# frc_operator_interface.net
KiCad netlist of a schematic drawn in EAGLE
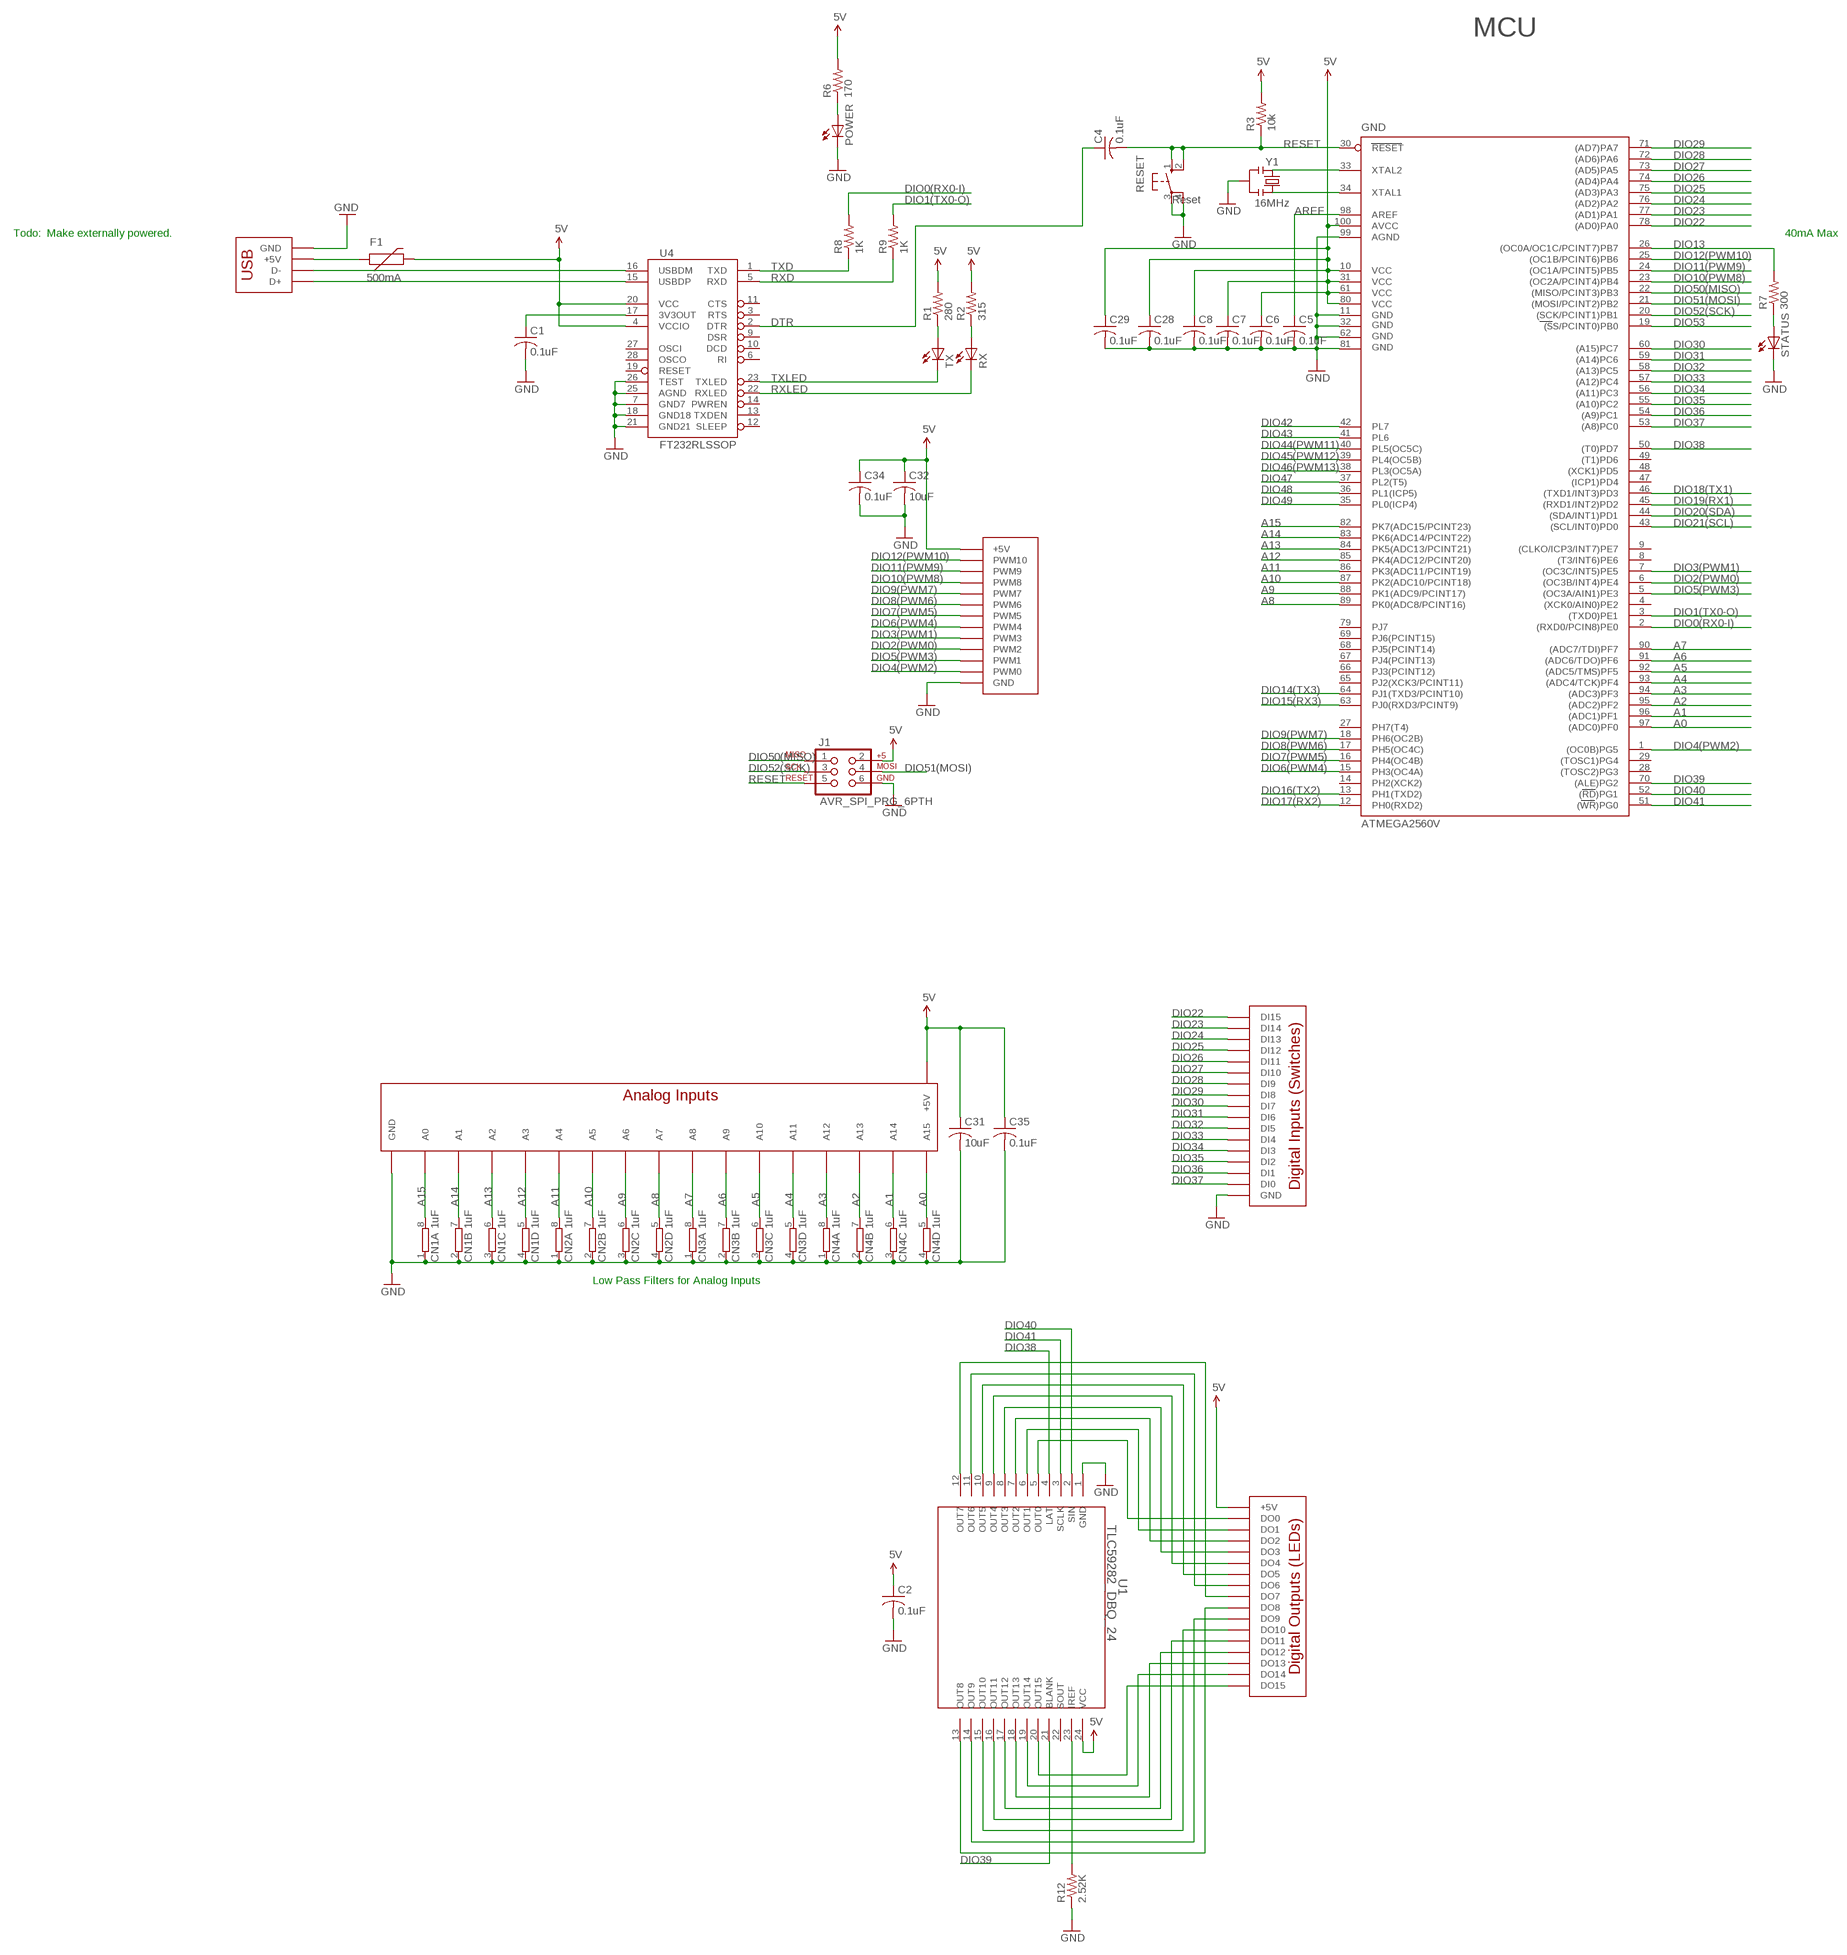
[diagram p0: schematic, sheet 1]

(export (version "E")
  (design (tool "Eeschema 10.0.6"))
  (components
    (comp (ref "C1")
      (value "0.1uF")
      (footprint "eagle-import:C1206")
      (libsource (lib "eagle-import") (part "C-USC1206"))
    )
    (comp (ref "C2")
      (value "0.1uF")
      (footprint "eagle-import:C1206")
      (libsource (lib "eagle-import") (part "C-USC1206"))
    )
    (comp (ref "C4")
      (value "0.1uF")
      (footprint "eagle-import:C1206")
      (libsource (lib "eagle-import") (part "C-USC1206"))
    )
    (comp (ref "C5")
      (value "0.1uF")
      (footprint "eagle-import:C1206")
      (libsource (lib "eagle-import") (part "C-USC1206"))
    )
    (comp (ref "C6")
      (value "0.1uF")
      (footprint "eagle-import:C1206")
      (libsource (lib "eagle-import") (part "C-USC1206"))
    )
    (comp (ref "C7")
      (value "0.1uF")
      (footprint "eagle-import:C1206")
      (libsource (lib "eagle-import") (part "C-USC1206"))
    )
    (comp (ref "C8")
      (value "0.1uF")
      (footprint "eagle-import:C1206")
      (libsource (lib "eagle-import") (part "C-USC1206"))
    )
    (comp (ref "C28")
      (value "0.1uF")
      (footprint "eagle-import:C1206")
      (libsource (lib "eagle-import") (part "C-USC1206"))
    )
    (comp (ref "C29")
      (value "0.1uF")
      (footprint "eagle-import:C1206")
      (libsource (lib "eagle-import") (part "C-USC1206"))
    )
    (comp (ref "C31")
      (value "10uF")
      (footprint "eagle-import:C1206")
      (libsource (lib "eagle-import") (part "C-USC1206"))
    )
    (comp (ref "C32")
      (value "10uF")
      (footprint "eagle-import:C1206")
      (libsource (lib "eagle-import") (part "C-USC1206"))
    )
    (comp (ref "C34")
      (value "0.1uF")
      (footprint "eagle-import:C1206")
      (libsource (lib "eagle-import") (part "C-USC1206"))
    )
    (comp (ref "C35")
      (value "0.1uF")
      (footprint "eagle-import:C1206")
      (libsource (lib "eagle-import") (part "C-USC1206"))
    )
    (comp (ref "CN1")
      (value "1uF")
      (footprint "eagle-import:EXB38V")
      (libsource (lib "eagle-import") (part "4R-NEXB38V"))
    )
    (comp (ref "CN2")
      (value "1uF")
      (footprint "eagle-import:EXB38V")
      (libsource (lib "eagle-import") (part "4R-NEXB38V"))
    )
    (comp (ref "CN3")
      (value "1uF")
      (footprint "eagle-import:EXB38V")
      (libsource (lib "eagle-import") (part "4R-NEXB38V"))
    )
    (comp (ref "CN4")
      (value "1uF")
      (footprint "eagle-import:EXB38V")
      (libsource (lib "eagle-import") (part "4R-NEXB38V"))
    )
    (comp (ref "F1")
      (value "500mA")
      (footprint "eagle-import:PTC-1206")
      (libsource (lib "eagle-import") (part "PTCSMD"))
    )
    (comp (ref "GND")
      (value "ATMEGA2560AU")
      (footprint "eagle-import:TQFP100")
      (libsource (lib "eagle-import") (part "ATMEGA2560AU"))
    )
    (comp (ref "J1")
      (value "AVR_SPI_PRG_6PTH")
      (footprint "eagle-import:2X3")
      (libsource (lib "eagle-import") (part "AVR_SPI_PRG_6PTH"))
    )
    (comp (ref "POWER")
      (value "LED3MM")
      (footprint "eagle-import:LED3MM")
      (libsource (lib "eagle-import") (part "LED3MM"))
    )
    (comp (ref "R1")
      (value "280")
      (footprint "eagle-import:M1206")
      (libsource (lib "eagle-import") (part "R-US_M1206"))
    )
    (comp (ref "R2")
      (value "315")
      (footprint "eagle-import:M1206")
      (libsource (lib "eagle-import") (part "R-US_M1206"))
    )
    (comp (ref "R3")
      (value "10k")
      (footprint "eagle-import:M1206")
      (libsource (lib "eagle-import") (part "R-US_M1206"))
    )
    (comp (ref "R6")
      (value "170")
      (footprint "eagle-import:M1206")
      (libsource (lib "eagle-import") (part "R-US_M1206"))
    )
    (comp (ref "R7")
      (value "300")
      (footprint "eagle-import:M1206")
      (libsource (lib "eagle-import") (part "R-US_M1206"))
    )
    (comp (ref "R8")
      (value "1K")
      (footprint "eagle-import:M1206")
      (libsource (lib "eagle-import") (part "R-US_M1206"))
    )
    (comp (ref "R9")
      (value "1K")
      (footprint "eagle-import:M1206")
      (libsource (lib "eagle-import") (part "R-US_M1206"))
    )
    (comp (ref "R12")
      (value "2.52K")
      (footprint "eagle-import:M1206")
      (libsource (lib "eagle-import") (part "R-US_M1206"))
    )
    (comp (ref "RESET")
      (value "10-XX")
      (footprint "eagle-import:B3F-10XX")
      (fields (field (name "MPN") "B3F-1000"))
      (libsource (lib "eagle-import") (part "10-XX"))
    )
    (comp (ref "RX")
      (value "LED3MM")
      (footprint "eagle-import:LED3MM")
      (libsource (lib "eagle-import") (part "LED3MM"))
    )
    (comp (ref "STATUS")
      (value "LED3MM")
      (footprint "eagle-import:LED3MM")
      (libsource (lib "eagle-import") (part "LED3MM"))
    )
    (comp (ref "TX")
      (value "LED3MM")
      (footprint "eagle-import:LED3MM")
      (libsource (lib "eagle-import") (part "LED3MM"))
    )
    (comp (ref "U$2")
      (value "DIGITALIN")
      (footprint "eagle-import:DIGITALIN")
      (libsource (lib "eagle-import") (part "DIGITALIN"))
    )
    (comp (ref "U$10")
      (value "PWMHEADER")
      (footprint "eagle-import:PWMHEADER")
      (libsource (lib "eagle-import") (part "PWMHEADER"))
    )
    (comp (ref "U$11")
      (value "DIGITALOUTPUTS")
      (footprint "eagle-import:DIGITALOUT")
      (libsource (lib "eagle-import") (part "DIGITALOUTPUTS"))
    )
    (comp (ref "U$12")
      (value "ANALOGHEADER")
      (footprint "eagle-import:ANALOGHEADER")
      (libsource (lib "eagle-import") (part "ANALOGHEADER"))
    )
    (comp (ref "U$14")
      (value "UE27BC54130-USB")
      (footprint "eagle-import:UE27BC54130-USB")
      (libsource (lib "eagle-import") (part "UE27BC54130-USB"))
    )
    (comp (ref "U1")
      (value "TLC59282_DBQ_24")
      (footprint "eagle-import:DBQ24")
      (fields
        (field (name "GENERIC_PART_NUMBER") "TLC59282")
        (field (name "MANUFACTURER") "Texas Instruments")
        (field (name "MANUFACTURER_PART_NUMBER") "tlc59282_dbq_24")
      )
      (libsource (lib "eagle-import") (part "TLC59282_DBQ_24"))
    )
    (comp (ref "U4")
      (value "FT232RLSSOP")
      (footprint "eagle-import:SSOP28DB")
      (libsource (lib "eagle-import") (part "FT232RLSSOP"))
    )
    (comp (ref "Y1")
      (value "RESONATORSMD")
      (footprint "eagle-import:RESONATOR-SMD")
      (libsource (lib "eagle-import") (part "RESONATORSMD"))
    )
  )
  (nets
    (net (code "1") (name "/A0") (class "Default")
      (node (ref "CN4") (pin "5") (pinfunction "2_5") (pintype "passive"))
      (node (ref "GND") (pin "97") (pinfunction "(ADC0)PF0_97") (pintype "bidirectional"))
      (node (ref "U$12") (pin "15") (pinfunction "A15_15") (pintype "bidirectional"))
    )
    (net (code "2") (name "/A1") (class "Default")
      (node (ref "CN4") (pin "6") (pinfunction "2_6") (pintype "passive"))
      (node (ref "GND") (pin "96") (pinfunction "(ADC1)PF1_96") (pintype "bidirectional"))
      (node (ref "U$12") (pin "14") (pinfunction "A14_14") (pintype "bidirectional"))
    )
    (net (code "3") (name "/A2") (class "Default")
      (node (ref "CN4") (pin "7") (pinfunction "2_7") (pintype "passive"))
      (node (ref "GND") (pin "95") (pinfunction "(ADC2)PF2_95") (pintype "bidirectional"))
      (node (ref "U$12") (pin "13") (pinfunction "A13_13") (pintype "bidirectional"))
    )
    (net (code "4") (name "/A3") (class "Default")
      (node (ref "CN4") (pin "8") (pinfunction "2_8") (pintype "passive"))
      (node (ref "GND") (pin "94") (pinfunction "(ADC3)PF3_94") (pintype "bidirectional"))
      (node (ref "U$12") (pin "12") (pinfunction "A12_12") (pintype "bidirectional"))
    )
    (net (code "5") (name "/A4") (class "Default")
      (node (ref "CN3") (pin "5") (pinfunction "2_5") (pintype "passive"))
      (node (ref "GND") (pin "93") (pinfunction "(ADC4/TCK)PF4_93") (pintype "bidirectional"))
      (node (ref "U$12") (pin "11") (pinfunction "A11_11") (pintype "bidirectional"))
    )
    (net (code "6") (name "/A5") (class "Default")
      (node (ref "CN3") (pin "6") (pinfunction "2_6") (pintype "passive"))
      (node (ref "GND") (pin "92") (pinfunction "(ADC5/TMS)PF5_92") (pintype "bidirectional"))
      (node (ref "U$12") (pin "10") (pinfunction "A10_10") (pintype "bidirectional"))
    )
    (net (code "7") (name "/A6") (class "Default")
      (node (ref "CN3") (pin "7") (pinfunction "2_7") (pintype "passive"))
      (node (ref "GND") (pin "91") (pinfunction "(ADC6/TDO)PF6_91") (pintype "bidirectional"))
      (node (ref "U$12") (pin "9") (pinfunction "A9_9") (pintype "bidirectional"))
    )
    (net (code "8") (name "/A7") (class "Default")
      (node (ref "CN3") (pin "8") (pinfunction "2_8") (pintype "passive"))
      (node (ref "GND") (pin "90") (pinfunction "(ADC7/TDI)PF7_90") (pintype "bidirectional"))
      (node (ref "U$12") (pin "8") (pinfunction "A8_8") (pintype "bidirectional"))
    )
    (net (code "9") (name "/A8") (class "Default")
      (node (ref "CN2") (pin "5") (pinfunction "2_5") (pintype "passive"))
      (node (ref "GND") (pin "89") (pinfunction "PK0(ADC8/PCINT16)_89") (pintype "bidirectional"))
      (node (ref "U$12") (pin "7") (pinfunction "A7_7") (pintype "bidirectional"))
    )
    (net (code "10") (name "/A9") (class "Default")
      (node (ref "CN2") (pin "6") (pinfunction "2_6") (pintype "passive"))
      (node (ref "GND") (pin "88") (pinfunction "PK1(ADC9/PCINT17)_88") (pintype "bidirectional"))
      (node (ref "U$12") (pin "6") (pinfunction "A6_6") (pintype "bidirectional"))
    )
    (net (code "11") (name "/A10") (class "Default")
      (node (ref "CN2") (pin "7") (pinfunction "2_7") (pintype "passive"))
      (node (ref "GND") (pin "87") (pinfunction "PK2(ADC10/PCINT18)_87") (pintype "bidirectional"))
      (node (ref "U$12") (pin "5") (pinfunction "A5_5") (pintype "bidirectional"))
    )
    (net (code "12") (name "/A11") (class "Default")
      (node (ref "CN2") (pin "8") (pinfunction "2_8") (pintype "passive"))
      (node (ref "GND") (pin "86") (pinfunction "PK3(ADC11/PCINT19)_86") (pintype "bidirectional"))
      (node (ref "U$12") (pin "4") (pinfunction "A4_4") (pintype "bidirectional"))
    )
    (net (code "13") (name "/A12") (class "Default")
      (node (ref "CN1") (pin "5") (pinfunction "2_5") (pintype "passive"))
      (node (ref "GND") (pin "85") (pinfunction "PK4(ADC12/PCINT20)_85") (pintype "bidirectional"))
      (node (ref "U$12") (pin "3") (pinfunction "A3_3") (pintype "bidirectional"))
    )
    (net (code "14") (name "/A13") (class "Default")
      (node (ref "CN1") (pin "6") (pinfunction "2_6") (pintype "passive"))
      (node (ref "GND") (pin "84") (pinfunction "PK5(ADC13/PCINT21)_84") (pintype "bidirectional"))
      (node (ref "U$12") (pin "2") (pinfunction "A2_2") (pintype "bidirectional"))
    )
    (net (code "15") (name "/A14") (class "Default")
      (node (ref "CN1") (pin "7") (pinfunction "2_7") (pintype "passive"))
      (node (ref "GND") (pin "83") (pinfunction "PK6(ADC14/PCINT22)_83") (pintype "bidirectional"))
      (node (ref "U$12") (pin "1") (pinfunction "A1_1") (pintype "bidirectional"))
    )
    (net (code "16") (name "/A15") (class "Default")
      (node (ref "CN1") (pin "8") (pinfunction "2_8") (pintype "passive"))
      (node (ref "GND") (pin "82") (pinfunction "PK7(ADC15/PCINT23)_82") (pintype "bidirectional"))
      (node (ref "U$12") (pin "0") (pinfunction "A0_0") (pintype "bidirectional"))
    )
    (net (code "17") (name "/AREF") (class "Default")
      (node (ref "C5") (pin "1") (pinfunction "1_1") (pintype "passive"))
      (node (ref "GND") (pin "98") (pinfunction "AREF_98") (pintype "bidirectional"))
    )
    (net (code "18") (name "/DIO0(RX0-I)") (class "Default")
      (node (ref "GND") (pin "2") (pinfunction "(RXD0/PCIN8)PE0_2") (pintype "bidirectional"))
      (node (ref "R8") (pin "2") (pinfunction "2_2") (pintype "passive"))
    )
    (net (code "19") (name "/DIO1(TX0-O)") (class "Default")
      (node (ref "GND") (pin "3") (pinfunction "(TXD0)PE1_3") (pintype "bidirectional"))
      (node (ref "R9") (pin "2") (pinfunction "2_2") (pintype "passive"))
    )
    (net (code "20") (name "/DIO2(PWM0)") (class "Default")
      (node (ref "GND") (pin "6") (pinfunction "(OC3B/INT4)PE4_6") (pintype "bidirectional"))
      (node (ref "U$10") (pin "2") (pinfunction "PWM2_2") (pintype "output"))
    )
    (net (code "21") (name "/DIO3(PWM1)") (class "Default")
      (node (ref "GND") (pin "7") (pinfunction "(OC3C/INT5)PE5_7") (pintype "bidirectional"))
      (node (ref "U$10") (pin "3") (pinfunction "PWM3_3") (pintype "output"))
    )
    (net (code "22") (name "/DIO4(PWM2)") (class "Default")
      (node (ref "GND") (pin "1") (pinfunction "(OC0B)PG5_1") (pintype "bidirectional"))
      (node (ref "U$10") (pin "0") (pinfunction "PWM0_0") (pintype "output"))
    )
    (net (code "23") (name "/DIO5(PWM3)") (class "Default")
      (node (ref "GND") (pin "5") (pinfunction "(OC3A/AIN1)PE3_5") (pintype "bidirectional"))
      (node (ref "U$10") (pin "1") (pinfunction "PWM1_1") (pintype "output"))
    )
    (net (code "24") (name "/DIO6(PWM4)") (class "Default")
      (node (ref "GND") (pin "15") (pinfunction "PH3(OC4A)_15") (pintype "bidirectional"))
      (node (ref "U$10") (pin "4") (pinfunction "PWM4_4") (pintype "output"))
    )
    (net (code "25") (name "/DIO7(PWM5)") (class "Default")
      (node (ref "GND") (pin "16") (pinfunction "PH4(OC4B)_16") (pintype "bidirectional"))
      (node (ref "U$10") (pin "5") (pinfunction "PWM5_5") (pintype "output"))
    )
    (net (code "26") (name "/DIO8(PWM6)") (class "Default")
      (node (ref "GND") (pin "17") (pinfunction "PH5(OC4C)_17") (pintype "bidirectional"))
      (node (ref "U$10") (pin "6") (pinfunction "PWM6_6") (pintype "output"))
    )
    (net (code "27") (name "/DIO9(PWM7)") (class "Default")
      (node (ref "GND") (pin "18") (pinfunction "PH6(OC2B)_18") (pintype "bidirectional"))
      (node (ref "U$10") (pin "7") (pinfunction "PWM7_7") (pintype "output"))
    )
    (net (code "28") (name "/DIO10(PWM8)") (class "Default")
      (node (ref "GND") (pin "23") (pinfunction "(OC2A/PCINT4)PB4_23") (pintype "bidirectional"))
      (node (ref "U$10") (pin "8") (pinfunction "PWM8_8") (pintype "output"))
    )
    (net (code "29") (name "/DIO11(PWM9)") (class "Default")
      (node (ref "GND") (pin "24") (pinfunction "(OC1A/PCINT5)PB5_24") (pintype "bidirectional"))
      (node (ref "U$10") (pin "9") (pinfunction "PWM9_9") (pintype "output"))
    )
    (net (code "30") (name "/DIO12(PWM10)") (class "Default")
      (node (ref "GND") (pin "25") (pinfunction "(OC1B/PCINT6)PB6_25") (pintype "bidirectional"))
      (node (ref "U$10") (pin "10") (pinfunction "PWM10_10") (pintype "output"))
    )
    (net (code "31") (name "/DIO13") (class "Default")
      (node (ref "GND") (pin "26") (pinfunction "(OC0A/OC1C/PCINT7)PB7_26") (pintype "bidirectional"))
      (node (ref "R7") (pin "2") (pinfunction "2_2") (pintype "passive"))
    )
    (net (code "32") (name "/DIO14(TX3)") (class "Default")
      (node (ref "GND") (pin "64") (pinfunction "PJ1(TXD3/PCINT10)_64") (pintype "bidirectional"))
    )
    (net (code "33") (name "/DIO15(RX3)") (class "Default")
      (node (ref "GND") (pin "63") (pinfunction "PJ0(RXD3/PCINT9)_63") (pintype "bidirectional"))
    )
    (net (code "34") (name "/DIO16(TX2)") (class "Default")
      (node (ref "GND") (pin "13") (pinfunction "PH1(TXD2)_13") (pintype "bidirectional"))
    )
    (net (code "35") (name "/DIO17(RX2)") (class "Default")
      (node (ref "GND") (pin "12") (pinfunction "PH0(RXD2)_12") (pintype "bidirectional"))
    )
    (net (code "36") (name "/DIO18(TX1)") (class "Default")
      (node (ref "GND") (pin "46") (pinfunction "(TXD1/INT3)PD3_46") (pintype "bidirectional"))
    )
    (net (code "37") (name "/DIO19(RX1)") (class "Default")
      (node (ref "GND") (pin "45") (pinfunction "(RXD1/INT2)PD2_45") (pintype "bidirectional"))
    )
    (net (code "38") (name "/DIO20(SDA)") (class "Default")
      (node (ref "GND") (pin "44") (pinfunction "(SDA/INT1)PD1_44") (pintype "bidirectional"))
    )
    (net (code "39") (name "/DIO21(SCL)") (class "Default")
      (node (ref "GND") (pin "43") (pinfunction "(SCL/INT0)PD0_43") (pintype "bidirectional"))
    )
    (net (code "40") (name "/DIO22") (class "Default")
      (node (ref "GND") (pin "78") (pinfunction "(AD0)PA0_78") (pintype "bidirectional"))
      (node (ref "U$2") (pin "DI15") (pinfunction "DI15_DI15") (pintype "bidirectional"))
    )
    (net (code "41") (name "/DIO23") (class "Default")
      (node (ref "GND") (pin "77") (pinfunction "(AD1)PA1_77") (pintype "bidirectional"))
      (node (ref "U$2") (pin "DI14") (pinfunction "DI14_DI14") (pintype "bidirectional"))
    )
    (net (code "42") (name "/DIO24") (class "Default")
      (node (ref "GND") (pin "76") (pinfunction "(AD2)PA2_76") (pintype "bidirectional"))
      (node (ref "U$2") (pin "DI13") (pinfunction "DI13_DI13") (pintype "bidirectional"))
    )
    (net (code "43") (name "/DIO25") (class "Default")
      (node (ref "GND") (pin "75") (pinfunction "(AD3)PA3_75") (pintype "bidirectional"))
      (node (ref "U$2") (pin "DI12") (pinfunction "DI12_DI12") (pintype "bidirectional"))
    )
    (net (code "44") (name "/DIO26") (class "Default")
      (node (ref "GND") (pin "74") (pinfunction "(AD4)PA4_74") (pintype "bidirectional"))
      (node (ref "U$2") (pin "DI11") (pinfunction "DI11_DI11") (pintype "bidirectional"))
    )
    (net (code "45") (name "/DIO27") (class "Default")
      (node (ref "GND") (pin "73") (pinfunction "(AD5)PA5_73") (pintype "bidirectional"))
      (node (ref "U$2") (pin "DI10") (pinfunction "DI10_DI10") (pintype "bidirectional"))
    )
    (net (code "46") (name "/DIO28") (class "Default")
      (node (ref "GND") (pin "72") (pinfunction "(AD6)PA6_72") (pintype "bidirectional"))
      (node (ref "U$2") (pin "DI9") (pinfunction "DI9_DI9") (pintype "bidirectional"))
    )
    (net (code "47") (name "/DIO29") (class "Default")
      (node (ref "GND") (pin "71") (pinfunction "(AD7)PA7_71") (pintype "bidirectional"))
      (node (ref "U$2") (pin "DI8") (pinfunction "DI8_DI8") (pintype "bidirectional"))
    )
    (net (code "48") (name "/DIO30") (class "Default")
      (node (ref "GND") (pin "60") (pinfunction "(A15)PC7_60") (pintype "bidirectional"))
      (node (ref "U$2") (pin "DI7") (pinfunction "DI7_DI7") (pintype "bidirectional"))
    )
    (net (code "49") (name "/DIO31") (class "Default")
      (node (ref "GND") (pin "59") (pinfunction "(A14)PC6_59") (pintype "bidirectional"))
      (node (ref "U$2") (pin "DI6") (pinfunction "DI6_DI6") (pintype "bidirectional"))
    )
    (net (code "50") (name "/DIO32") (class "Default")
      (node (ref "GND") (pin "58") (pinfunction "(A13)PC5_58") (pintype "bidirectional"))
      (node (ref "U$2") (pin "DI5") (pinfunction "DI5_DI5") (pintype "bidirectional"))
    )
    (net (code "51") (name "/DIO33") (class "Default")
      (node (ref "GND") (pin "57") (pinfunction "(A12)PC4_57") (pintype "bidirectional"))
      (node (ref "U$2") (pin "DI4") (pinfunction "DI4_DI4") (pintype "bidirectional"))
    )
    (net (code "52") (name "/DIO34") (class "Default")
      (node (ref "GND") (pin "56") (pinfunction "(A11)PC3_56") (pintype "bidirectional"))
      (node (ref "U$2") (pin "DI3") (pinfunction "DI3_DI3") (pintype "bidirectional"))
    )
    (net (code "53") (name "/DIO35") (class "Default")
      (node (ref "GND") (pin "55") (pinfunction "(A10)PC2_55") (pintype "bidirectional"))
      (node (ref "U$2") (pin "DI2") (pinfunction "DI2_DI2") (pintype "bidirectional"))
    )
    (net (code "54") (name "/DIO36") (class "Default")
      (node (ref "GND") (pin "54") (pinfunction "(A9)PC1_54") (pintype "bidirectional"))
      (node (ref "U$2") (pin "DI1") (pinfunction "DI1_DI1") (pintype "bidirectional"))
    )
    (net (code "55") (name "/DIO37") (class "Default")
      (node (ref "GND") (pin "53") (pinfunction "(A8)PC0_53") (pintype "bidirectional"))
      (node (ref "U$2") (pin "DI0") (pinfunction "DI0_DI0") (pintype "bidirectional"))
    )
    (net (code "56") (name "/DIO38") (class "Default")
      (node (ref "GND") (pin "50") (pinfunction "(T0)PD7_50") (pintype "bidirectional"))
      (node (ref "U1") (pin "4") (pinfunction "LAT_4") (pintype "input"))
    )
    (net (code "57") (name "/DIO39") (class "Default")
      (node (ref "GND") (pin "70") (pinfunction "(ALE)PG2_70") (pintype "bidirectional"))
      (node (ref "U1") (pin "21") (pinfunction "BLANK_21") (pintype "input"))
    )
    (net (code "58") (name "/DIO40") (class "Default")
      (node (ref "GND") (pin "52") (pinfunction "(RD)PG1_52") (pintype "bidirectional"))
      (node (ref "U1") (pin "2") (pinfunction "SIN_2") (pintype "input"))
    )
    (net (code "59") (name "/DIO41") (class "Default")
      (node (ref "GND") (pin "51") (pinfunction "(WR)PG0_51") (pintype "bidirectional"))
      (node (ref "U1") (pin "3") (pinfunction "SCLK_3") (pintype "input"))
    )
    (net (code "60") (name "/DIO42") (class "Default")
      (node (ref "GND") (pin "42") (pinfunction "PL7_42") (pintype "bidirectional"))
    )
    (net (code "61") (name "/DIO43") (class "Default")
      (node (ref "GND") (pin "41") (pinfunction "PL6_41") (pintype "bidirectional"))
    )
    (net (code "62") (name "/DIO44(PWM11)") (class "Default")
      (node (ref "GND") (pin "40") (pinfunction "PL5(OC5C)_40") (pintype "bidirectional"))
    )
    (net (code "63") (name "/DIO45(PWM12)") (class "Default")
      (node (ref "GND") (pin "39") (pinfunction "PL4(OC5B)_39") (pintype "bidirectional"))
    )
    (net (code "64") (name "/DIO46(PWM13)") (class "Default")
      (node (ref "GND") (pin "38") (pinfunction "PL3(OC5A)_38") (pintype "bidirectional"))
    )
    (net (code "65") (name "/DIO47") (class "Default")
      (node (ref "GND") (pin "37") (pinfunction "PL2(T5)_37") (pintype "bidirectional"))
    )
    (net (code "66") (name "/DIO48") (class "Default")
      (node (ref "GND") (pin "36") (pinfunction "PL1(ICP5)_36") (pintype "bidirectional"))
    )
    (net (code "67") (name "/DIO49") (class "Default")
      (node (ref "GND") (pin "35") (pinfunction "PL0(ICP4)_35") (pintype "bidirectional"))
    )
    (net (code "68") (name "/DIO50(MISO)") (class "Default")
      (node (ref "GND") (pin "22") (pinfunction "(MISO/PCINT3)PB3_22") (pintype "bidirectional"))
      (node (ref "J1") (pin "1") (pinfunction "1_1") (pintype "passive"))
    )
    (net (code "69") (name "/DIO51(MOSI)") (class "Default")
      (node (ref "GND") (pin "21") (pinfunction "(MOSI/PCINT2)PB2_21") (pintype "bidirectional"))
      (node (ref "J1") (pin "4") (pinfunction "4_4") (pintype "passive"))
    )
    (net (code "70") (name "/DIO52(SCK)") (class "Default")
      (node (ref "GND") (pin "20") (pinfunction "(SCK/PCINT1)PB1_20") (pintype "bidirectional"))
      (node (ref "J1") (pin "3") (pinfunction "3_3") (pintype "passive"))
    )
    (net (code "71") (name "/DIO53") (class "Default")
      (node (ref "GND") (pin "19") (pinfunction "(SS/PCINT0)PB0_19") (pintype "bidirectional"))
    )
    (net (code "72") (name "/DTR") (class "Default")
      (node (ref "C4") (pin "1") (pinfunction "1_1") (pintype "passive"))
      (node (ref "U4") (pin "2") (pinfunction "DTR_2") (pintype "output"))
    )
    (net (code "73") (name "/RESET") (class "Default")
      (node (ref "C4") (pin "2") (pinfunction "2_2") (pintype "passive"))
      (node (ref "GND") (pin "30") (pinfunction "RESET_30") (pintype "input"))
      (node (ref "J1") (pin "5") (pinfunction "5_5") (pintype "passive"))
      (node (ref "R3") (pin "1") (pinfunction "1_1") (pintype "passive"))
      (node (ref "RESET") (pin "1") (pinfunction "S_1") (pintype "passive"))
      (node (ref "RESET") (pin "2") (pinfunction "S1_2") (pintype "passive"))
    )
    (net (code "74") (name "/RXD") (class "Default")
      (node (ref "R9") (pin "1") (pinfunction "1_1") (pintype "passive"))
      (node (ref "U4") (pin "5") (pinfunction "RXD_5") (pintype "input"))
    )
    (net (code "75") (name "/RXLED") (class "Default")
      (node (ref "RX") (pin "K") (pinfunction "C_K") (pintype "passive"))
      (node (ref "U4") (pin "22") (pinfunction "RXLED_22") (pintype "input"))
    )
    (net (code "76") (name "/TXD") (class "Default")
      (node (ref "R8") (pin "1") (pinfunction "1_1") (pintype "passive"))
      (node (ref "U4") (pin "1") (pinfunction "TXD_1") (pintype "output"))
    )
    (net (code "77") (name "/TXLED") (class "Default")
      (node (ref "TX") (pin "K") (pinfunction "C_K") (pintype "passive"))
      (node (ref "U4") (pin "23") (pinfunction "TXLED_23") (pintype "input"))
    )
    (net (code "78") (name "5V") (class "Default")
      (node (ref "C2") (pin "1") (pinfunction "1_1") (pintype "passive"))
      (node (ref "C28") (pin "1") (pinfunction "1_1") (pintype "passive"))
      (node (ref "C29") (pin "1") (pinfunction "1_1") (pintype "passive"))
      (node (ref "C31") (pin "1") (pinfunction "1_1") (pintype "passive"))
      (node (ref "C32") (pin "1") (pinfunction "1_1") (pintype "passive"))
      (node (ref "C34") (pin "1") (pinfunction "1_1") (pintype "passive"))
      (node (ref "C35") (pin "1") (pinfunction "1_1") (pintype "passive"))
      (node (ref "C6") (pin "1") (pinfunction "1_1") (pintype "passive"))
      (node (ref "C7") (pin "1") (pinfunction "1_1") (pintype "passive"))
      (node (ref "C8") (pin "1") (pinfunction "1_1") (pintype "passive"))
      (node (ref "F1") (pin "2") (pinfunction "2_2") (pintype "bidirectional"))
      (node (ref "GND") (pin "10") (pinfunction "VCC_10") (pintype "power_in"))
      (node (ref "GND") (pin "100") (pinfunction "AVCC_100") (pintype "power_in"))
      (node (ref "GND") (pin "31") (pinfunction "VCC1_31") (pintype "power_in"))
      (node (ref "GND") (pin "61") (pinfunction "VCC2_61") (pintype "power_in"))
      (node (ref "GND") (pin "80") (pinfunction "VCC3_80") (pintype "power_in"))
      (node (ref "J1") (pin "2") (pinfunction "2_2") (pintype "passive"))
      (node (ref "R1") (pin "2") (pinfunction "2_2") (pintype "passive"))
      (node (ref "R2") (pin "2") (pinfunction "2_2") (pintype "passive"))
      (node (ref "R3") (pin "2") (pinfunction "2_2") (pintype "passive"))
      (node (ref "R6") (pin "2") (pinfunction "2_2") (pintype "passive"))
      (node (ref "U$10") (pin "+5V@10") (pinfunction "+5V_+5V@10") (pintype "power_in"))
      (node (ref "U$10") (pin "+5V@11") (pinfunction "+5V_+5V@11") (pintype "power_in"))
      (node (ref "U$10") (pin "+5V@12") (pinfunction "+5V_+5V@12") (pintype "power_in"))
      (node (ref "U$10") (pin "+5V@13") (pinfunction "+5V_+5V@13") (pintype "power_in"))
      (node (ref "U$10") (pin "+5V@3") (pinfunction "+5V_+5V@3") (pintype "power_in"))
      (node (ref "U$10") (pin "+5V@4") (pinfunction "+5V_+5V@4") (pintype "power_in"))
      (node (ref "U$10") (pin "+5V@5") (pinfunction "+5V_+5V@5") (pintype "power_in"))
      (node (ref "U$10") (pin "+5V@6") (pinfunction "+5V_+5V@6") (pintype "power_in"))
      (node (ref "U$10") (pin "+5V@7") (pinfunction "+5V_+5V@7") (pintype "power_in"))
      (node (ref "U$10") (pin "+5V@8") (pinfunction "+5V_+5V@8") (pintype "power_in"))
      (node (ref "U$10") (pin "+5V@9") (pinfunction "+5V_+5V@9") (pintype "power_in"))
      (node (ref "U$11") (pin "+5V@0") (pinfunction "+5V_+5V@0") (pintype "power_in"))
      (node (ref "U$11") (pin "+5V@1") (pinfunction "+5V_+5V@1") (pintype "power_in"))
      (node (ref "U$11") (pin "+5V@10") (pinfunction "+5V_+5V@10") (pintype "power_in"))
      (node (ref "U$11") (pin "+5V@11") (pinfunction "+5V_+5V@11") (pintype "power_in"))
      (node (ref "U$11") (pin "+5V@12") (pinfunction "+5V_+5V@12") (pintype "power_in"))
      (node (ref "U$11") (pin "+5V@13") (pinfunction "+5V_+5V@13") (pintype "power_in"))
      (node (ref "U$11") (pin "+5V@14") (pinfunction "+5V_+5V@14") (pintype "power_in"))
      (node (ref "U$11") (pin "+5V@15") (pinfunction "+5V_+5V@15") (pintype "power_in"))
      (node (ref "U$11") (pin "+5V@2") (pinfunction "+5V_+5V@2") (pintype "power_in"))
      (node (ref "U$11") (pin "+5V@3") (pinfunction "+5V_+5V@3") (pintype "power_in"))
      (node (ref "U$11") (pin "+5V@4") (pinfunction "+5V_+5V@4") (pintype "power_in"))
      (node (ref "U$11") (pin "+5V@5") (pinfunction "+5V_+5V@5") (pintype "power_in"))
      (node (ref "U$11") (pin "+5V@6") (pinfunction "+5V_+5V@6") (pintype "power_in"))
      (node (ref "U$11") (pin "+5V@7") (pinfunction "+5V_+5V@7") (pintype "power_in"))
      (node (ref "U$11") (pin "+5V@8") (pinfunction "+5V_+5V@8") (pintype "power_in"))
      (node (ref "U$11") (pin "+5V@9") (pinfunction "+5V_+5V@9") (pintype "power_in"))
      (node (ref "U$12") (pin "+5V@0") (pinfunction "+5V_+5V@0") (pintype "bidirectional"))
      (node (ref "U$12") (pin "+5V@1") (pinfunction "+5V_+5V@1") (pintype "bidirectional"))
      (node (ref "U$12") (pin "+5V@10") (pinfunction "+5V_+5V@10") (pintype "bidirectional"))
      (node (ref "U$12") (pin "+5V@11") (pinfunction "+5V_+5V@11") (pintype "bidirectional"))
      (node (ref "U$12") (pin "+5V@12") (pinfunction "+5V_+5V@12") (pintype "bidirectional"))
      (node (ref "U$12") (pin "+5V@13") (pinfunction "+5V_+5V@13") (pintype "bidirectional"))
      (node (ref "U$12") (pin "+5V@14") (pinfunction "+5V_+5V@14") (pintype "bidirectional"))
      (node (ref "U$12") (pin "+5V@15") (pinfunction "+5V_+5V@15") (pintype "bidirectional"))
      (node (ref "U$12") (pin "+5V@2") (pinfunction "+5V_+5V@2") (pintype "bidirectional"))
      (node (ref "U$12") (pin "+5V@3") (pinfunction "+5V_+5V@3") (pintype "bidirectional"))
      (node (ref "U$12") (pin "+5V@4") (pinfunction "+5V_+5V@4") (pintype "bidirectional"))
      (node (ref "U$12") (pin "+5V@5") (pinfunction "+5V_+5V@5") (pintype "bidirectional"))
      (node (ref "U$12") (pin "+5V@6") (pinfunction "+5V_+5V@6") (pintype "bidirectional"))
      (node (ref "U$12") (pin "+5V@7") (pinfunction "+5V_+5V@7") (pintype "bidirectional"))
      (node (ref "U$12") (pin "+5V@8") (pinfunction "+5V_+5V@8") (pintype "bidirectional"))
      (node (ref "U$12") (pin "+5V@9") (pinfunction "+5V_+5V@9") (pintype "bidirectional"))
      (node (ref "U1") (pin "24") (pinfunction "VCC_24") (pintype "power_in"))
      (node (ref "U4") (pin "20") (pinfunction "VCC_20") (pintype "power_in"))
      (node (ref "U4") (pin "4") (pinfunction "VCCIO_4") (pintype "power_in"))
    )
    (net (code "79") (name "GND") (class "Default")
      (node (ref "C1") (pin "2") (pinfunction "2_2") (pintype "passive"))
      (node (ref "C2") (pin "2") (pinfunction "2_2") (pintype "passive"))
      (node (ref "C28") (pin "2") (pinfunction "2_2") (pintype "passive"))
      (node (ref "C29") (pin "2") (pinfunction "2_2") (pintype "passive"))
      (node (ref "C31") (pin "2") (pinfunction "2_2") (pintype "passive"))
      (node (ref "C32") (pin "2") (pinfunction "2_2") (pintype "passive"))
      (node (ref "C34") (pin "2") (pinfunction "2_2") (pintype "passive"))
      (node (ref "C35") (pin "2") (pinfunction "2_2") (pintype "passive"))
      (node (ref "C5") (pin "2") (pinfunction "2_2") (pintype "passive"))
      (node (ref "C6") (pin "2") (pinfunction "2_2") (pintype "passive"))
      (node (ref "C7") (pin "2") (pinfunction "2_2") (pintype "passive"))
      (node (ref "C8") (pin "2") (pinfunction "2_2") (pintype "passive"))
      (node (ref "CN1") (pin "1") (pinfunction "1_1") (pintype "passive"))
      (node (ref "CN1") (pin "2") (pinfunction "1_2") (pintype "passive"))
      (node (ref "CN1") (pin "3") (pinfunction "1_3") (pintype "passive"))
      (node (ref "CN1") (pin "4") (pinfunction "1_4") (pintype "passive"))
      (node (ref "CN2") (pin "1") (pinfunction "1_1") (pintype "passive"))
      (node (ref "CN2") (pin "2") (pinfunction "1_2") (pintype "passive"))
      (node (ref "CN2") (pin "3") (pinfunction "1_3") (pintype "passive"))
      (node (ref "CN2") (pin "4") (pinfunction "1_4") (pintype "passive"))
      (node (ref "CN3") (pin "1") (pinfunction "1_1") (pintype "passive"))
      (node (ref "CN3") (pin "2") (pinfunction "1_2") (pintype "passive"))
      (node (ref "CN3") (pin "3") (pinfunction "1_3") (pintype "passive"))
      (node (ref "CN3") (pin "4") (pinfunction "1_4") (pintype "passive"))
      (node (ref "CN4") (pin "1") (pinfunction "1_1") (pintype "passive"))
      (node (ref "CN4") (pin "2") (pinfunction "1_2") (pintype "passive"))
      (node (ref "CN4") (pin "3") (pinfunction "1_3") (pintype "passive"))
      (node (ref "CN4") (pin "4") (pinfunction "1_4") (pintype "passive"))
      (node (ref "GND") (pin "11") (pinfunction "GND_11") (pintype "power_in"))
      (node (ref "GND") (pin "32") (pinfunction "GND1_32") (pintype "power_in"))
      (node (ref "GND") (pin "62") (pinfunction "GND2_62") (pintype "power_in"))
      (node (ref "GND") (pin "81") (pinfunction "GND3_81") (pintype "power_in"))
      (node (ref "GND") (pin "99") (pinfunction "AGND_99") (pintype "power_in"))
      (node (ref "J1") (pin "6") (pinfunction "6_6") (pintype "passive"))
      (node (ref "POWER") (pin "K") (pinfunction "C_K") (pintype "passive"))
      (node (ref "R12") (pin "1") (pinfunction "1_1") (pintype "passive"))
      (node (ref "RESET") (pin "3") (pinfunction "P_3") (pintype "passive"))
      (node (ref "RESET") (pin "4") (pinfunction "P1_4") (pintype "passive"))
      (node (ref "STATUS") (pin "K") (pinfunction "C_K") (pintype "passive"))
      (node (ref "U$10") (pin "GND@10") (pinfunction "GND_GND@10") (pintype "power_in"))
      (node (ref "U$10") (pin "GND@11") (pinfunction "GND_GND@11") (pintype "power_in"))
      (node (ref "U$10") (pin "GND@12") (pinfunction "GND_GND@12") (pintype "power_in"))
      (node (ref "U$10") (pin "GND@13") (pinfunction "GND_GND@13") (pintype "power_in"))
      (node (ref "U$10") (pin "GND@3") (pinfunction "GND_GND@3") (pintype "power_in"))
      (node (ref "U$10") (pin "GND@4") (pinfunction "GND_GND@4") (pintype "power_in"))
      (node (ref "U$10") (pin "GND@5") (pinfunction "GND_GND@5") (pintype "power_in"))
      (node (ref "U$10") (pin "GND@6") (pinfunction "GND_GND@6") (pintype "power_in"))
      (node (ref "U$10") (pin "GND@7") (pinfunction "GND_GND@7") (pintype "power_in"))
      (node (ref "U$10") (pin "GND@8") (pinfunction "GND_GND@8") (pintype "power_in"))
      (node (ref "U$10") (pin "GND@9") (pinfunction "GND_GND@9") (pintype "power_in"))
      (node (ref "U$12") (pin "GND@0") (pinfunction "GND_GND@0") (pintype "bidirectional"))
      (node (ref "U$12") (pin "GND@1") (pinfunction "GND_GND@1") (pintype "bidirectional"))
      (node (ref "U$12") (pin "GND@10") (pinfunction "GND_GND@10") (pintype "bidirectional"))
      (node (ref "U$12") (pin "GND@11") (pinfunction "GND_GND@11") (pintype "bidirectional"))
      (node (ref "U$12") (pin "GND@12") (pinfunction "GND_GND@12") (pintype "bidirectional"))
      (node (ref "U$12") (pin "GND@13") (pinfunction "GND_GND@13") (pintype "bidirectional"))
      (node (ref "U$12") (pin "GND@14") (pinfunction "GND_GND@14") (pintype "bidirectional"))
      (node (ref "U$12") (pin "GND@15") (pinfunction "GND_GND@15") (pintype "bidirectional"))
      (node (ref "U$12") (pin "GND@2") (pinfunction "GND_GND@2") (pintype "bidirectional"))
      (node (ref "U$12") (pin "GND@3") (pinfunction "GND_GND@3") (pintype "bidirectional"))
      (node (ref "U$12") (pin "GND@4") (pinfunction "GND_GND@4") (pintype "bidirectional"))
      (node (ref "U$12") (pin "GND@5") (pinfunction "GND_GND@5") (pintype "bidirectional"))
      (node (ref "U$12") (pin "GND@6") (pinfunction "GND_GND@6") (pintype "bidirectional"))
      (node (ref "U$12") (pin "GND@7") (pinfunction "GND_GND@7") (pintype "bidirectional"))
      (node (ref "U$12") (pin "GND@8") (pinfunction "GND_GND@8") (pintype "bidirectional"))
      (node (ref "U$12") (pin "GND@9") (pinfunction "GND_GND@9") (pintype "bidirectional"))
      (node (ref "U$14") (pin "GND@0") (pinfunction "GND_GND@0") (pintype "power_in"))
      (node (ref "U$14") (pin "GND@1") (pinfunction "GND_GND@1") (pintype "power_in"))
      (node (ref "U$14") (pin "GND@2") (pinfunction "GND_GND@2") (pintype "power_in"))
      (node (ref "U$2") (pin "GND@0") (pinfunction "GND_GND@0") (pintype "power_in"))
      (node (ref "U$2") (pin "GND@1") (pinfunction "GND_GND@1") (pintype "power_in"))
      (node (ref "U$2") (pin "GND@10") (pinfunction "GND_GND@10") (pintype "power_in"))
      (node (ref "U$2") (pin "GND@11") (pinfunction "GND_GND@11") (pintype "power_in"))
      (node (ref "U$2") (pin "GND@12") (pinfunction "GND_GND@12") (pintype "power_in"))
      (node (ref "U$2") (pin "GND@13") (pinfunction "GND_GND@13") (pintype "power_in"))
      (node (ref "U$2") (pin "GND@14") (pinfunction "GND_GND@14") (pintype "power_in"))
      (node (ref "U$2") (pin "GND@15") (pinfunction "GND_GND@15") (pintype "power_in"))
      (node (ref "U$2") (pin "GND@2") (pinfunction "GND_GND@2") (pintype "power_in"))
      (node (ref "U$2") (pin "GND@3") (pinfunction "GND_GND@3") (pintype "power_in"))
      (node (ref "U$2") (pin "GND@4") (pinfunction "GND_GND@4") (pintype "power_in"))
      (node (ref "U$2") (pin "GND@5") (pinfunction "GND_GND@5") (pintype "power_in"))
      (node (ref "U$2") (pin "GND@6") (pinfunction "GND_GND@6") (pintype "power_in"))
      (node (ref "U$2") (pin "GND@7") (pinfunction "GND_GND@7") (pintype "power_in"))
      (node (ref "U$2") (pin "GND@8") (pinfunction "GND_GND@8") (pintype "power_in"))
      (node (ref "U$2") (pin "GND@9") (pinfunction "GND_GND@9") (pintype "power_in"))
      (node (ref "U1") (pin "1") (pinfunction "GND_1") (pintype "power_in"))
      (node (ref "U4") (pin "18") (pinfunction "GND18_18") (pintype "power_in"))
      (node (ref "U4") (pin "21") (pinfunction "GND21_21") (pintype "power_in"))
      (node (ref "U4") (pin "25") (pinfunction "AGND_25") (pintype "power_in"))
      (node (ref "U4") (pin "26") (pinfunction "TEST_26") (pintype "input"))
      (node (ref "U4") (pin "7") (pinfunction "GND7_7") (pintype "power_in"))
      (node (ref "Y1") (pin "2") (pinfunction "2_2") (pintype "passive"))
    )
    (net (code "80") (name "Net-(F1-Pad1)") (class "Default")
      (node (ref "F1") (pin "1") (pinfunction "1_1") (pintype "bidirectional"))
      (node (ref "U$14") (pin "+5V") (pinfunction "+5V_+5V") (pintype "power_in"))
    )
    (net (code "81") (name "Net-(GND-XTAL1)") (class "Default")
      (node (ref "GND") (pin "34") (pinfunction "XTAL1_34") (pintype "input"))
      (node (ref "Y1") (pin "3") (pinfunction "3_3") (pintype "passive"))
    )
    (net (code "82") (name "Net-(GND-XTAL2)") (class "Default")
      (node (ref "GND") (pin "33") (pinfunction "XTAL2_33") (pintype "output"))
      (node (ref "Y1") (pin "1") (pinfunction "1_1") (pintype "passive"))
    )
    (net (code "83") (name "Net-(POWER-PadA)") (class "Default")
      (node (ref "POWER") (pin "A") (pinfunction "A_A") (pintype "passive"))
      (node (ref "R6") (pin "1") (pinfunction "1_1") (pintype "passive"))
    )
    (net (code "84") (name "Net-(R1-Pad1)") (class "Default")
      (node (ref "R1") (pin "1") (pinfunction "1_1") (pintype "passive"))
      (node (ref "TX") (pin "A") (pinfunction "A_A") (pintype "passive"))
    )
    (net (code "85") (name "Net-(R2-Pad1)") (class "Default")
      (node (ref "R2") (pin "1") (pinfunction "1_1") (pintype "passive"))
      (node (ref "RX") (pin "A") (pinfunction "A_A") (pintype "passive"))
    )
    (net (code "86") (name "Net-(R7-Pad1)") (class "Default")
      (node (ref "R7") (pin "1") (pinfunction "1_1") (pintype "passive"))
      (node (ref "STATUS") (pin "A") (pinfunction "A_A") (pintype "passive"))
    )
    (net (code "87") (name "Net-(U$14-D+)") (class "Default")
      (node (ref "U$14") (pin "+DATA") (pinfunction "D+_+DATA") (pintype "bidirectional"))
      (node (ref "U4") (pin "15") (pinfunction "USBDP_15") (pintype "bidirectional"))
    )
    (net (code "88") (name "Net-(U$14-D-)") (class "Default")
      (node (ref "U$14") (pin "-DATA") (pinfunction "D-_-DATA") (pintype "bidirectional"))
      (node (ref "U4") (pin "16") (pinfunction "USBDM_16") (pintype "bidirectional"))
    )
    (net (code "89") (name "Net-(U1-IREF)") (class "Default")
      (node (ref "R12") (pin "2") (pinfunction "2_2") (pintype "passive"))
      (node (ref "U1") (pin "23") (pinfunction "IREF_23") (pintype "bidirectional"))
    )
    (net (code "90") (name "Net-(U1-OUT0)") (class "Default")
      (node (ref "U$11") (pin "DO0") (pinfunction "DO0_DO0") (pintype "bidirectional"))
      (node (ref "U1") (pin "5") (pinfunction "OUT0_5") (pintype "output"))
    )
    (net (code "91") (name "Net-(U1-OUT1)") (class "Default")
      (node (ref "U$11") (pin "DO1") (pinfunction "DO1_DO1") (pintype "bidirectional"))
      (node (ref "U1") (pin "6") (pinfunction "OUT1_6") (pintype "output"))
    )
    (net (code "92") (name "Net-(U1-OUT2)") (class "Default")
      (node (ref "U$11") (pin "DO2") (pinfunction "DO2_DO2") (pintype "bidirectional"))
      (node (ref "U1") (pin "7") (pinfunction "OUT2_7") (pintype "output"))
    )
    (net (code "93") (name "Net-(U1-OUT3)") (class "Default")
      (node (ref "U$11") (pin "DO3") (pinfunction "DO3_DO3") (pintype "bidirectional"))
      (node (ref "U1") (pin "8") (pinfunction "OUT3_8") (pintype "output"))
    )
    (net (code "94") (name "Net-(U1-OUT4)") (class "Default")
      (node (ref "U$11") (pin "DO4") (pinfunction "DO4_DO4") (pintype "bidirectional"))
      (node (ref "U1") (pin "9") (pinfunction "OUT4_9") (pintype "output"))
    )
    (net (code "95") (name "Net-(U1-OUT5)") (class "Default")
      (node (ref "U$11") (pin "DO5") (pinfunction "DO5_DO5") (pintype "bidirectional"))
      (node (ref "U1") (pin "10") (pinfunction "OUT5_10") (pintype "output"))
    )
    (net (code "96") (name "Net-(U1-OUT6)") (class "Default")
      (node (ref "U$11") (pin "DO6") (pinfunction "DO6_DO6") (pintype "bidirectional"))
      (node (ref "U1") (pin "11") (pinfunction "OUT6_11") (pintype "output"))
    )
    (net (code "97") (name "Net-(U1-OUT7)") (class "Default")
      (node (ref "U$11") (pin "DO7") (pinfunction "DO7_DO7") (pintype "bidirectional"))
      (node (ref "U1") (pin "12") (pinfunction "OUT7_12") (pintype "output"))
    )
    (net (code "98") (name "Net-(U1-OUT8)") (class "Default")
      (node (ref "U$11") (pin "DO8") (pinfunction "DO8_DO8") (pintype "bidirectional"))
      (node (ref "U1") (pin "13") (pinfunction "OUT8_13") (pintype "output"))
    )
    (net (code "99") (name "Net-(U1-OUT9)") (class "Default")
      (node (ref "U$11") (pin "DO9") (pinfunction "DO9_DO9") (pintype "bidirectional"))
      (node (ref "U1") (pin "14") (pinfunction "OUT9_14") (pintype "output"))
    )
    (net (code "100") (name "Net-(U1-OUT10)") (class "Default")
      (node (ref "U$11") (pin "DO10") (pinfunction "DO10_DO10") (pintype "bidirectional"))
      (node (ref "U1") (pin "15") (pinfunction "OUT10_15") (pintype "output"))
    )
    (net (code "101") (name "Net-(U1-OUT11)") (class "Default")
      (node (ref "U$11") (pin "DO11") (pinfunction "DO11_DO11") (pintype "bidirectional"))
      (node (ref "U1") (pin "16") (pinfunction "OUT11_16") (pintype "output"))
    )
    (net (code "102") (name "Net-(U1-OUT12)") (class "Default")
      (node (ref "U$11") (pin "DO12") (pinfunction "DO12_DO12") (pintype "bidirectional"))
      (node (ref "U1") (pin "17") (pinfunction "OUT12_17") (pintype "output"))
    )
    (net (code "103") (name "Net-(U1-OUT13)") (class "Default")
      (node (ref "U$11") (pin "DO13") (pinfunction "DO13_DO13") (pintype "bidirectional"))
      (node (ref "U1") (pin "18") (pinfunction "OUT13_18") (pintype "output"))
    )
    (net (code "104") (name "Net-(U1-OUT14)") (class "Default")
      (node (ref "U$11") (pin "DO14") (pinfunction "DO14_DO14") (pintype "bidirectional"))
      (node (ref "U1") (pin "19") (pinfunction "OUT14_19") (pintype "output"))
    )
    (net (code "105") (name "Net-(U1-OUT15)") (class "Default")
      (node (ref "U$11") (pin "DO15") (pinfunction "DO15_DO15") (pintype "bidirectional"))
      (node (ref "U1") (pin "20") (pinfunction "OUT15_20") (pintype "output"))
    )
    (net (code "106") (name "Net-(U4-3V3OUT)") (class "Default")
      (node (ref "C1") (pin "1") (pinfunction "1_1") (pintype "passive"))
      (node (ref "U4") (pin "17") (pinfunction "3V3OUT_17") (pintype "output"))
    )
    (net (code "107") (name "unconnected-(GND-(CLKO{slash}ICP3{slash}INT7)PE7-Pad9)") (class "Default")
      (node (ref "GND") (pin "9") (pinfunction "(CLKO/ICP3/INT7)PE7_9") (pintype "bidirectional"))
    )
    (net (code "108") (name "unconnected-(GND-(ICP1)PD4-Pad47)") (class "Default")
      (node (ref "GND") (pin "47") (pinfunction "(ICP1)PD4_47") (pintype "bidirectional"))
    )
    (net (code "109") (name "unconnected-(GND-(T1)PD6-Pad49)") (class "Default")
      (node (ref "GND") (pin "49") (pinfunction "(T1)PD6_49") (pintype "bidirectional"))
    )
    (net (code "110") (name "unconnected-(GND-(T3{slash}INT6)PE6-Pad8)") (class "Default")
      (node (ref "GND") (pin "8") (pinfunction "(T3/INT6)PE6_8") (pintype "bidirectional"))
    )
    (net (code "111") (name "unconnected-(GND-(TOSC1)PG4-Pad29)") (class "Default")
      (node (ref "GND") (pin "29") (pinfunction "(TOSC1)PG4_29") (pintype "bidirectional"))
    )
    (net (code "112") (name "unconnected-(GND-(TOSC2)PG3-Pad28)") (class "Default")
      (node (ref "GND") (pin "28") (pinfunction "(TOSC2)PG3_28") (pintype "bidirectional"))
    )
    (net (code "113") (name "unconnected-(GND-(XCK0{slash}AIN0)PE2-Pad4)") (class "Default")
      (node (ref "GND") (pin "4") (pinfunction "(XCK0/AIN0)PE2_4") (pintype "bidirectional"))
    )
    (net (code "114") (name "unconnected-(GND-(XCK1)PD5-Pad48)") (class "Default")
      (node (ref "GND") (pin "48") (pinfunction "(XCK1)PD5_48") (pintype "bidirectional"))
    )
    (net (code "115") (name "unconnected-(GND-PH2(XCK2)-Pad14)") (class "Default")
      (node (ref "GND") (pin "14") (pinfunction "PH2(XCK2)_14") (pintype "bidirectional"))
    )
    (net (code "116") (name "unconnected-(GND-PH7(T4)-Pad27)") (class "Default")
      (node (ref "GND") (pin "27") (pinfunction "PH7(T4)_27") (pintype "bidirectional"))
    )
    (net (code "117") (name "unconnected-(GND-PJ2(XCK3{slash}PCINT11)-Pad65)") (class "Default")
      (node (ref "GND") (pin "65") (pinfunction "PJ2(XCK3/PCINT11)_65") (pintype "bidirectional"))
    )
    (net (code "118") (name "unconnected-(GND-PJ3(PCINT12)-Pad66)") (class "Default")
      (node (ref "GND") (pin "66") (pinfunction "PJ3(PCINT12)_66") (pintype "bidirectional"))
    )
    (net (code "119") (name "unconnected-(GND-PJ4(PCINT13)-Pad67)") (class "Default")
      (node (ref "GND") (pin "67") (pinfunction "PJ4(PCINT13)_67") (pintype "bidirectional"))
    )
    (net (code "120") (name "unconnected-(GND-PJ5(PCINT14)-Pad68)") (class "Default")
      (node (ref "GND") (pin "68") (pinfunction "PJ5(PCINT14)_68") (pintype "bidirectional"))
    )
    (net (code "121") (name "unconnected-(GND-PJ6(PCINT15)-Pad69)") (class "Default")
      (node (ref "GND") (pin "69") (pinfunction "PJ6(PCINT15)_69") (pintype "bidirectional"))
    )
    (net (code "122") (name "unconnected-(GND-PJ7-Pad79)") (class "Default")
      (node (ref "GND") (pin "79") (pinfunction "PJ7_79") (pintype "bidirectional"))
    )
    (net (code "123") (name "unconnected-(U1-SOUT-Pad22)") (class "Default")
      (node (ref "U1") (pin "22") (pinfunction "SOUT_22") (pintype "output"))
    )
    (net (code "124") (name "unconnected-(U4-CTS-Pad11)") (class "Default")
      (node (ref "U4") (pin "11") (pinfunction "CTS_11") (pintype "input"))
    )
    (net (code "125") (name "unconnected-(U4-DCD-Pad10)") (class "Default")
      (node (ref "U4") (pin "10") (pinfunction "DCD_10") (pintype "input"))
    )
    (net (code "126") (name "unconnected-(U4-DSR-Pad9)") (class "Default")
      (node (ref "U4") (pin "9") (pinfunction "DSR_9") (pintype "input"))
    )
    (net (code "127") (name "unconnected-(U4-OSCI-Pad27)") (class "Default")
      (node (ref "U4") (pin "27") (pinfunction "OSCI_27") (pintype "input"))
    )
    (net (code "128") (name "unconnected-(U4-OSCO-Pad28)") (class "Default")
      (node (ref "U4") (pin "28") (pinfunction "OSCO_28") (pintype "output"))
    )
    (net (code "129") (name "unconnected-(U4-PWREN-Pad14)") (class "Default")
      (node (ref "U4") (pin "14") (pinfunction "PWREN_14") (pintype "input"))
    )
    (net (code "130") (name "unconnected-(U4-RESET-Pad19)") (class "Default")
      (node (ref "U4") (pin "19") (pinfunction "RESET_19") (pintype "input"))
    )
    (net (code "131") (name "unconnected-(U4-RI-Pad6)") (class "Default")
      (node (ref "U4") (pin "6") (pinfunction "RI_6") (pintype "input"))
    )
    (net (code "132") (name "unconnected-(U4-RTS-Pad3)") (class "Default")
      (node (ref "U4") (pin "3") (pinfunction "RTS_3") (pintype "output"))
    )
    (net (code "133") (name "unconnected-(U4-SLEEP-Pad12)") (class "Default")
      (node (ref "U4") (pin "12") (pinfunction "SLEEP_12") (pintype "input"))
    )
    (net (code "134") (name "unconnected-(U4-TXDEN-Pad13)") (class "Default")
      (node (ref "U4") (pin "13") (pinfunction "TXDEN_13") (pintype "input"))
    )
  )
)
